# plug_in_boards.net
KiCad netlist of a schematic drawn in EAGLE
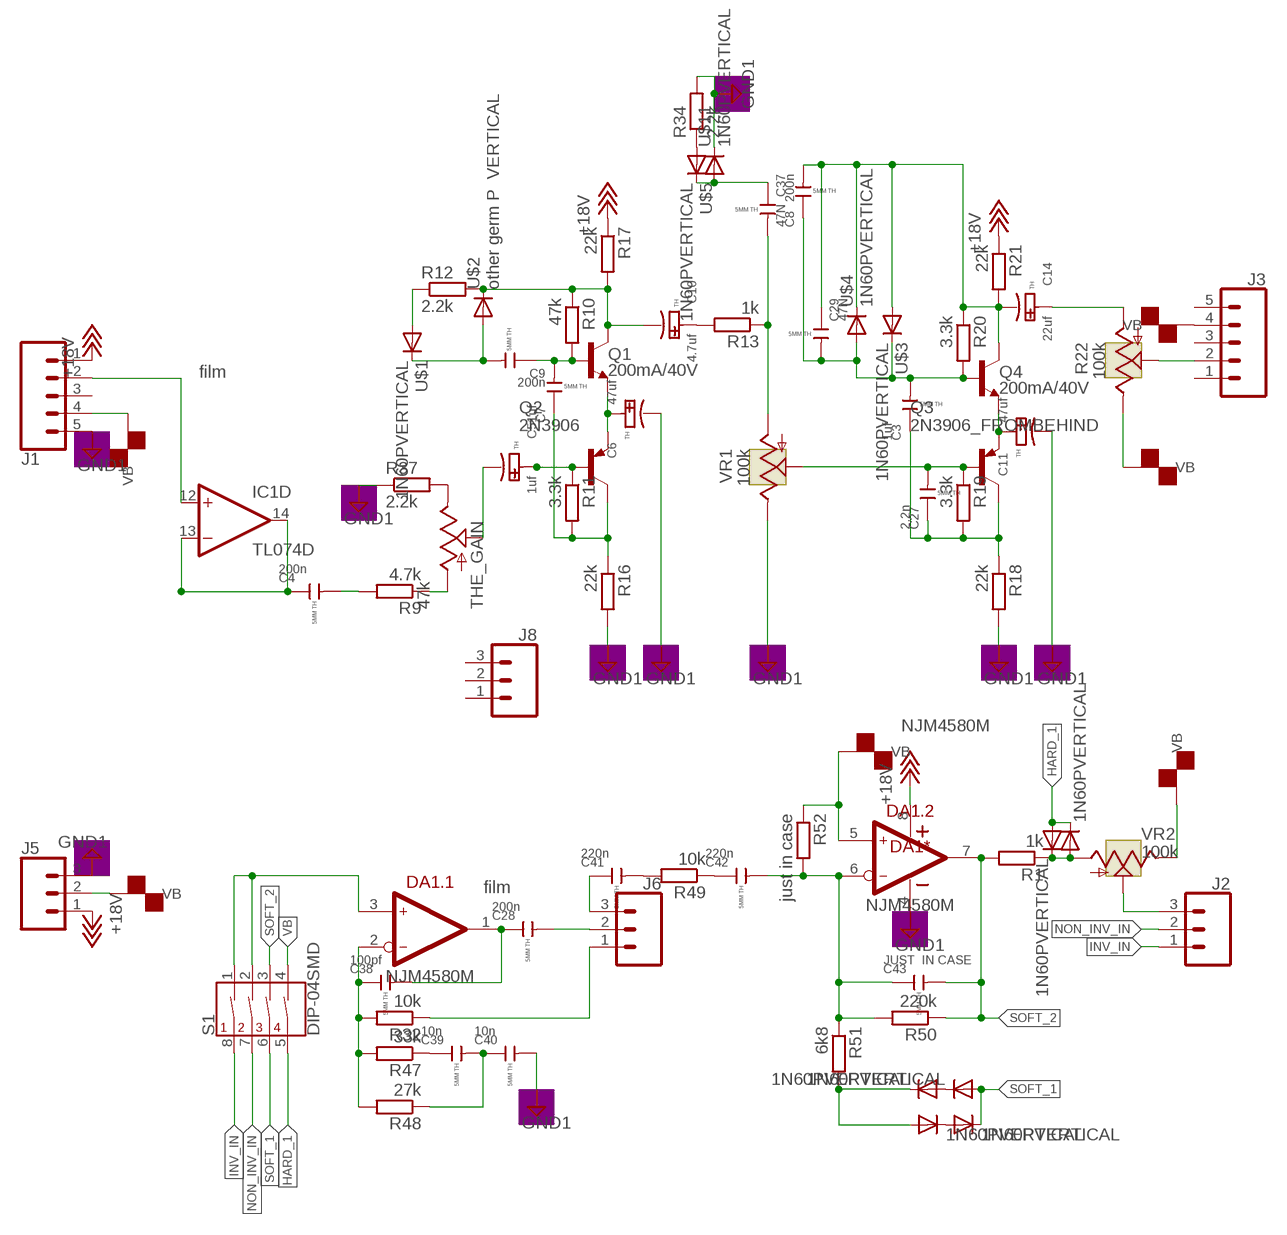
[diagram p0: schematic, sheet 1]

(export (version "E")
  (design (tool "Eeschema 10.0.6"))
  (components
    (comp (ref "C3")
      (value "1uf")
      (footprint "eagle-import:CERAMIC-5MM")
      (fields (field (name "PACKAGE") "5MM TH"))
      (libsource (lib "eagle-import") (part "THRU_HOLE_5MM_SPACING"))
    )
    (comp (ref "C4")
      (value "200n")
      (footprint "eagle-import:CERAMIC-5MM")
      (fields (field (name "PACKAGE") "5MM TH"))
      (libsource (lib "eagle-import") (part "THRU_HOLE_5MM_SPACING"))
    )
    (comp (ref "C5")
      (value "1uf")
      (footprint "eagle-import:PC-D5.3MM")
      (fields (field (name "PACKAGE") "TH"))
      (libsource (lib "eagle-import") (part "THRU-HOLE-POLARIZED"))
    )
    (comp (ref "C6")
      (value "47uf")
      (footprint "eagle-import:PC-D5.3MM")
      (fields (field (name "PACKAGE") "TH"))
      (libsource (lib "eagle-import") (part "THRU-HOLE-POLARIZED"))
    )
    (comp (ref "C7")
      (value "1uf")
      (footprint "eagle-import:CERAMIC-5MM")
      (fields (field (name "PACKAGE") "5MM TH"))
      (libsource (lib "eagle-import") (part "THRU_HOLE_5MM_SPACING"))
    )
    (comp (ref "C8")
      (value "47N")
      (footprint "eagle-import:CERAMIC-5MM")
      (fields (field (name "PACKAGE") "5MM TH"))
      (libsource (lib "eagle-import") (part "THRU_HOLE_5MM_SPACING"))
    )
    (comp (ref "C9")
      (value "200n")
      (footprint "eagle-import:CERAMIC-5MM")
      (fields (field (name "PACKAGE") "5MM TH"))
      (libsource (lib "eagle-import") (part "THRU_HOLE_5MM_SPACING"))
    )
    (comp (ref "C10")
      (value "4.7uf")
      (footprint "eagle-import:PC-D5.3MM")
      (fields (field (name "PACKAGE") "TH"))
      (libsource (lib "eagle-import") (part "THRU-HOLE-POLARIZED"))
    )
    (comp (ref "C11")
      (value "47uf")
      (footprint "eagle-import:PC-D5.3MM")
      (fields (field (name "PACKAGE") "TH"))
      (libsource (lib "eagle-import") (part "THRU-HOLE-POLARIZED"))
    )
    (comp (ref "C14")
      (value "22uf")
      (footprint "eagle-import:PC-D5.3MM")
      (fields (field (name "PACKAGE") "TH"))
      (libsource (lib "eagle-import") (part "THRU-HOLE-POLARIZED"))
    )
    (comp (ref "C27")
      (value "2.2n")
      (footprint "eagle-import:CERAMIC-5MM")
      (fields (field (name "PACKAGE") "5MM TH"))
      (libsource (lib "eagle-import") (part "THRU_HOLE_5MM_SPACING"))
    )
    (comp (ref "C28")
      (value "200n")
      (footprint "eagle-import:CERAMIC-5MM")
      (fields (field (name "PACKAGE") "5MM TH"))
      (libsource (lib "eagle-import") (part "THRU_HOLE_5MM_SPACING"))
    )
    (comp (ref "C29")
      (value "47N")
      (footprint "eagle-import:CERAMIC-5MM")
      (fields (field (name "PACKAGE") "5MM TH"))
      (libsource (lib "eagle-import") (part "THRU_HOLE_5MM_SPACING"))
    )
    (comp (ref "C37")
      (value "200n")
      (footprint "eagle-import:CERAMIC-5MM")
      (fields (field (name "PACKAGE") "5MM TH"))
      (libsource (lib "eagle-import") (part "THRU_HOLE_5MM_SPACING"))
    )
    (comp (ref "C38")
      (value "100pf")
      (footprint "eagle-import:CERAMIC-5MM")
      (fields (field (name "PACKAGE") "5MM TH"))
      (libsource (lib "eagle-import") (part "THRU_HOLE_5MM_SPACING"))
    )
    (comp (ref "C39")
      (value "10n")
      (footprint "eagle-import:CERAMIC-5MM")
      (fields (field (name "PACKAGE") "5MM TH"))
      (libsource (lib "eagle-import") (part "THRU_HOLE_5MM_SPACING"))
    )
    (comp (ref "C40")
      (value "10n")
      (footprint "eagle-import:CERAMIC-5MM")
      (fields (field (name "PACKAGE") "5MM TH"))
      (libsource (lib "eagle-import") (part "THRU_HOLE_5MM_SPACING"))
    )
    (comp (ref "C41")
      (value "220n")
      (footprint "eagle-import:CERAMIC-5MM")
      (fields (field (name "PACKAGE") "5MM TH"))
      (libsource (lib "eagle-import") (part "THRU_HOLE_5MM_SPACING"))
    )
    (comp (ref "C42")
      (value "220n")
      (footprint "eagle-import:CERAMIC-5MM")
      (fields (field (name "PACKAGE") "5MM TH"))
      (libsource (lib "eagle-import") (part "THRU_HOLE_5MM_SPACING"))
    )
    (comp (ref "C43")
      (value "JUST IN CASE")
      (footprint "eagle-import:CERAMIC-5MM")
      (fields (field (name "PACKAGE") "5MM TH"))
      (libsource (lib "eagle-import") (part "THRU_HOLE_5MM_SPACING"))
    )
    (comp (ref "DA1")
      (value "NJM4580M")
      (footprint "eagle-import:SO-8")
      (libsource (lib "eagle-import") (part "NJM4580M"))
    )
    (comp (ref "IC1")
      (value "TL074D")
      (footprint "eagle-import:SO14")
      (libsource (lib "eagle-import") (part "TL074D"))
    )
    (comp (ref "J1")
      (value "CONN_05PTH_LONGPADS")
      (footprint "eagle-import:1X05_LONGPADS")
      (libsource (lib "eagle-import") (part "CONN_05PTH_LONGPADS"))
    )
    (comp (ref "J2")
      (value "CONN_03LONGPADS")
      (footprint "eagle-import:1X03_LONGPADS")
      (libsource (lib "eagle-import") (part "CONN_03LONGPADS"))
    )
    (comp (ref "J3")
      (value "CONN_05PTH_LONGPADS")
      (footprint "eagle-import:1X05_LONGPADS")
      (libsource (lib "eagle-import") (part "CONN_05PTH_LONGPADS"))
    )
    (comp (ref "J5")
      (value "CONN_03LONGPADS")
      (footprint "eagle-import:1X03_LONGPADS")
      (libsource (lib "eagle-import") (part "CONN_03LONGPADS"))
    )
    (comp (ref "J6")
      (value "CONN_03LONGPADS")
      (footprint "eagle-import:1X03_LONGPADS")
      (libsource (lib "eagle-import") (part "CONN_03LONGPADS"))
    )
    (comp (ref "J8")
      (value "CONN_03LONGPADS")
      (footprint "eagle-import:1X03_LONGPADS")
      (libsource (lib "eagle-import") (part "CONN_03LONGPADS"))
    )
    (comp (ref "Q1")
      (value "200mA/40V")
      (footprint "eagle-import:TO-92")
      (libsource (lib "eagle-import") (part "TRANS_NPN-2N3904"))
    )
    (comp (ref "Q2")
      (value "2N3906")
      (footprint "eagle-import:TO92")
      (libsource (lib "eagle-import") (part "transistor-pnp_399_2N3906"))
    )
    (comp (ref "Q3")
      (value "2N3906_FROMBEHIND")
      (footprint "eagle-import:TO92")
      (libsource (lib "eagle-import") (part "2N3906"))
    )
    (comp (ref "Q4")
      (value "200mA/40V")
      (footprint "eagle-import:TO-92")
      (libsource (lib "eagle-import") (part "TRANS_NPN-2N3904"))
    )
    (comp (ref "R1")
      (value "1k")
      (footprint "eagle-import:R1206")
      (libsource (lib "eagle-import") (part "R-EU_R1206"))
    )
    (comp (ref "R9")
      (value "4.7k")
      (footprint "eagle-import:R1206")
      (libsource (lib "eagle-import") (part "R-EU_R1206"))
    )
    (comp (ref "R10")
      (value "47k")
      (footprint "eagle-import:R1206")
      (libsource (lib "eagle-import") (part "R-EU_R1206"))
    )
    (comp (ref "R11")
      (value "3.3k")
      (footprint "eagle-import:R1206")
      (libsource (lib "eagle-import") (part "R-EU_R1206"))
    )
    (comp (ref "R12")
      (value "2.2k")
      (footprint "eagle-import:R1206")
      (libsource (lib "eagle-import") (part "R-EU_R1206"))
    )
    (comp (ref "R13")
      (value "1k")
      (footprint "eagle-import:R1206")
      (libsource (lib "eagle-import") (part "R-EU_R1206"))
    )
    (comp (ref "R16")
      (value "22k")
      (footprint "eagle-import:R1206")
      (libsource (lib "eagle-import") (part "R-EU_R1206"))
    )
    (comp (ref "R17")
      (value "22k")
      (footprint "eagle-import:R1206")
      (libsource (lib "eagle-import") (part "R-EU_R1206"))
    )
    (comp (ref "R18")
      (value "22k")
      (footprint "eagle-import:R1206")
      (libsource (lib "eagle-import") (part "R-EU_R1206"))
    )
    (comp (ref "R19")
      (value "3.3k")
      (footprint "eagle-import:R1206")
      (libsource (lib "eagle-import") (part "R-EU_R1206"))
    )
    (comp (ref "R20")
      (value "3.3k")
      (footprint "eagle-import:R1206")
      (libsource (lib "eagle-import") (part "R-EU_R1206"))
    )
    (comp (ref "R21")
      (value "22k")
      (footprint "eagle-import:R1206")
      (libsource (lib "eagle-import") (part "R-EU_R1206"))
    )
    (comp (ref "R22")
      (value "100k")
      (footprint "eagle-import:3223G")
      (libsource (lib "eagle-import") (part "TRIM_US-3223G"))
    )
    (comp (ref "R32")
      (value "10k")
      (footprint "eagle-import:R1206")
      (libsource (lib "eagle-import") (part "R-EU_R1206"))
    )
    (comp (ref "R34")
      (value "2.2k")
      (footprint "eagle-import:R1206")
      (libsource (lib "eagle-import") (part "R-EU_R1206"))
    )
    (comp (ref "R37")
      (value "2.2k")
      (footprint "eagle-import:R1206")
      (libsource (lib "eagle-import") (part "R-EU_R1206"))
    )
    (comp (ref "R47")
      (value "33k")
      (footprint "eagle-import:R1206")
      (libsource (lib "eagle-import") (part "R-EU_R1206"))
    )
    (comp (ref "R48")
      (value "27k")
      (footprint "eagle-import:R1206")
      (libsource (lib "eagle-import") (part "R-EU_R1206"))
    )
    (comp (ref "R49")
      (value "10k")
      (footprint "eagle-import:R1206")
      (libsource (lib "eagle-import") (part "R-EU_R1206"))
    )
    (comp (ref "R50")
      (value "220k")
      (footprint "eagle-import:R1206")
      (libsource (lib "eagle-import") (part "R-EU_R1206"))
    )
    (comp (ref "R51")
      (value "6k8")
      (footprint "eagle-import:R1206")
      (libsource (lib "eagle-import") (part "R-EU_R1206"))
    )
    (comp (ref "R52")
      (value "just in case")
      (footprint "eagle-import:R1206")
      (libsource (lib "eagle-import") (part "R-EU_R1206"))
    )
    (comp (ref "S1")
      (value "DIP-04SMD")
      (footprint "eagle-import:DIPSWITCH-04-SMD")
      (libsource (lib "eagle-import") (part "DIP-04SMD"))
    )
    (comp (ref "THE_GAIN")
      (value "47k")
      (footprint "eagle-import:ALPS_POT")
      (libsource (lib "eagle-import") (part "POT"))
    )
    (comp (ref "U$1")
      (value "1N60PVERTICAL")
      (footprint "eagle-import:DO41-1")
      (libsource (lib "eagle-import") (part "1N60PVERTICAL"))
    )
    (comp (ref "U$2")
      (value "other germ P VERTICAL")
      (footprint "eagle-import:DO41-1")
      (libsource (lib "eagle-import") (part "1N60PVERTICAL"))
    )
    (comp (ref "U$3")
      (value "1N60PVERTICAL")
      (footprint "eagle-import:DO41-1")
      (libsource (lib "eagle-import") (part "1N60PVERTICAL"))
    )
    (comp (ref "U$4")
      (value "1N60PVERTICAL")
      (footprint "eagle-import:DO41-1")
      (libsource (lib "eagle-import") (part "1N60PVERTICAL"))
    )
    (comp (ref "U$5")
      (value "1N60PVERTICAL")
      (footprint "eagle-import:DO41-1")
      (libsource (lib "eagle-import") (part "1N60PVERTICAL"))
    )
    (comp (ref "U$9")
      (value "1N60PVERTICAL")
      (footprint "eagle-import:DO41-1")
      (libsource (lib "eagle-import") (part "1N60PVERTICAL"))
    )
    (comp (ref "U$11")
      (value "1N60PVERTICAL")
      (footprint "eagle-import:DO41-1")
      (libsource (lib "eagle-import") (part "1N60PVERTICAL"))
    )
    (comp (ref "U$12")
      (value "1N60PVERTICAL")
      (footprint "eagle-import:DO41-1")
      (libsource (lib "eagle-import") (part "1N60PVERTICAL"))
    )
    (comp (ref "U$26")
      (value "1N60PVERTICAL")
      (footprint "eagle-import:DO41-1")
      (libsource (lib "eagle-import") (part "1N60PVERTICAL"))
    )
    (comp (ref "U$27")
      (value "1N60PVERTICAL")
      (footprint "eagle-import:DO41-1")
      (libsource (lib "eagle-import") (part "1N60PVERTICAL"))
    )
    (comp (ref "U$28")
      (value "1N60PVERTICAL")
      (footprint "eagle-import:DO41-1")
      (libsource (lib "eagle-import") (part "1N60PVERTICAL"))
    )
    (comp (ref "U$29")
      (value "1N60PVERTICAL")
      (footprint "eagle-import:DO41-1")
      (libsource (lib "eagle-import") (part "1N60PVERTICAL"))
    )
    (comp (ref "VR1")
      (value "100k")
      (footprint "eagle-import:3223G")
      (libsource (lib "eagle-import") (part "TRIM_US-3223G"))
    )
    (comp (ref "VR2")
      (value "100k")
      (footprint "eagle-import:3223G")
      (libsource (lib "eagle-import") (part "TRIM_US-3223G"))
    )
  )
  (nets
    (net (code "1") (name "+18V") (class "Default")
      (node (ref "DA1") (pin "8") (pinfunction "V+_8") (pintype "power_in"))
      (node (ref "J1") (pin "1") (pinfunction "1_1") (pintype "passive"))
      (node (ref "J5") (pin "1") (pinfunction "1_1") (pintype "passive"))
      (node (ref "R17") (pin "1") (pinfunction "1_1") (pintype "passive"))
      (node (ref "R21") (pin "1") (pinfunction "1_1") (pintype "passive"))
    )
    (net (code "2") (name "GND1") (class "Default")
      (node (ref "C11") (pin "-") (pinfunction "-_-") (pintype "passive"))
      (node (ref "C40") (pin "2") (pinfunction "2_2") (pintype "passive"))
      (node (ref "C6") (pin "-") (pinfunction "-_-") (pintype "passive"))
      (node (ref "DA1") (pin "4") (pinfunction "V-_4") (pintype "power_in"))
      (node (ref "J1") (pin "5") (pinfunction "5_5") (pintype "passive"))
      (node (ref "J5") (pin "3") (pinfunction "3_3") (pintype "passive"))
      (node (ref "R16") (pin "2") (pinfunction "2_2") (pintype "passive"))
      (node (ref "R18") (pin "2") (pinfunction "2_2") (pintype "passive"))
      (node (ref "R34") (pin "2") (pinfunction "2_2") (pintype "passive"))
      (node (ref "R37") (pin "1") (pinfunction "1_1") (pintype "passive"))
      (node (ref "U$11") (pin "C") (pinfunction "C_C") (pintype "passive"))
      (node (ref "VR1") (pin "3") (pinfunction "E_3") (pintype "passive"))
    )
    (net (code "3") (name "HARD_1") (class "Default")
      (node (ref "S1") (pin "5") (pinfunction "4B_5") (pintype "bidirectional"))
      (node (ref "U$12") (pin "C") (pinfunction "C_C") (pintype "passive"))
      (node (ref "U$9") (pin "A") (pinfunction "A_A") (pintype "passive"))
    )
    (net (code "4") (name "INV_IN") (class "Default")
      (node (ref "J2") (pin "1") (pinfunction "1_1") (pintype "passive"))
      (node (ref "S1") (pin "8") (pinfunction "1B_8") (pintype "bidirectional"))
    )
    (net (code "5") (name "NON_INV_IN") (class "Default")
      (node (ref "J2") (pin "2") (pinfunction "2_2") (pintype "passive"))
      (node (ref "S1") (pin "7") (pinfunction "2B_7") (pintype "bidirectional"))
    )
    (net (code "6") (name "Net-(C4-Pad2)") (class "Default")
      (node (ref "C4") (pin "2") (pinfunction "2_2") (pintype "passive"))
      (node (ref "R9") (pin "2") (pinfunction "2_2") (pintype "passive"))
    )
    (net (code "7") (name "Net-(C9-Pad2)") (class "Default")
      (node (ref "C9") (pin "2") (pinfunction "2_2") (pintype "passive"))
      (node (ref "U$1") (pin "C") (pinfunction "C_C") (pintype "passive"))
      (node (ref "U$2") (pin "A") (pinfunction "A_A") (pintype "passive"))
    )
    (net (code "8") (name "Net-(C10-Pad+)") (class "Default")
      (node (ref "C10") (pin "+") (pinfunction "+_+") (pintype "passive"))
      (node (ref "R13") (pin "2") (pinfunction "2_2") (pintype "passive"))
    )
    (net (code "9") (name "Net-(C28-Pad2)") (class "Default")
      (node (ref "C28") (pin "2") (pinfunction "2_2") (pintype "passive"))
      (node (ref "J6") (pin "2") (pinfunction "2_2") (pintype "passive"))
    )
    (net (code "10") (name "Net-(C37-Pad1)") (class "Default")
      (node (ref "C37") (pin "1") (pinfunction "1_1") (pintype "passive"))
      (node (ref "U$11") (pin "A") (pinfunction "A_A") (pintype "passive"))
      (node (ref "U$5") (pin "C") (pinfunction "C_C") (pintype "passive"))
    )
    (net (code "11") (name "Net-(C39-Pad1)") (class "Default")
      (node (ref "C39") (pin "1") (pinfunction "1_1") (pintype "passive"))
      (node (ref "R47") (pin "1") (pinfunction "1_1") (pintype "passive"))
    )
    (net (code "12") (name "Net-(C39-Pad2)") (class "Default")
      (node (ref "C39") (pin "2") (pinfunction "2_2") (pintype "passive"))
      (node (ref "C40") (pin "1") (pinfunction "1_1") (pintype "passive"))
      (node (ref "R48") (pin "1") (pinfunction "1_1") (pintype "passive"))
    )
    (net (code "13") (name "Net-(C41-Pad1)") (class "Default")
      (node (ref "C41") (pin "1") (pinfunction "1_1") (pintype "passive"))
      (node (ref "J6") (pin "3") (pinfunction "3_3") (pintype "passive"))
    )
    (net (code "14") (name "Net-(C41-Pad2)") (class "Default")
      (node (ref "C41") (pin "2") (pinfunction "2_2") (pintype "passive"))
      (node (ref "R49") (pin "2") (pinfunction "2_2") (pintype "passive"))
    )
    (net (code "15") (name "Net-(C42-Pad1)") (class "Default")
      (node (ref "C42") (pin "1") (pinfunction "1_1") (pintype "passive"))
      (node (ref "R49") (pin "1") (pinfunction "1_1") (pintype "passive"))
    )
    (net (code "16") (name "Net-(DA1B-IN+)") (class "Default")
      (node (ref "DA1") (pin "3") (pinfunction "IN+_3") (pintype "input"))
      (node (ref "S1") (pin "1") (pinfunction "1A_1") (pintype "bidirectional"))
      (node (ref "S1") (pin "2") (pinfunction "2A_2") (pintype "bidirectional"))
    )
    (net (code "17") (name "Net-(DA1B-IN-)") (class "Default")
      (node (ref "C38") (pin "1") (pinfunction "1_1") (pintype "passive"))
      (node (ref "DA1") (pin "2") (pinfunction "IN-_2") (pintype "input"))
      (node (ref "R32") (pin "2") (pinfunction "2_2") (pintype "passive"))
      (node (ref "R47") (pin "2") (pinfunction "2_2") (pintype "passive"))
      (node (ref "R48") (pin "2") (pinfunction "2_2") (pintype "passive"))
    )
    (net (code "18") (name "Net-(DA1B-OUT)") (class "Default")
      (node (ref "C28") (pin "1") (pinfunction "1_1") (pintype "passive"))
      (node (ref "C38") (pin "2") (pinfunction "2_2") (pintype "passive"))
      (node (ref "DA1") (pin "1") (pinfunction "OUT_1") (pintype "output"))
    )
    (net (code "19") (name "Net-(DA1C-IN-)") (class "Default")
      (node (ref "C42") (pin "2") (pinfunction "2_2") (pintype "passive"))
      (node (ref "C43") (pin "1") (pinfunction "1_1") (pintype "passive"))
      (node (ref "DA1") (pin "6") (pinfunction "IN-_6") (pintype "input"))
      (node (ref "R50") (pin "2") (pinfunction "2_2") (pintype "passive"))
      (node (ref "R51") (pin "1") (pinfunction "1_1") (pintype "passive"))
      (node (ref "R52") (pin "2") (pinfunction "2_2") (pintype "passive"))
    )
    (net (code "20") (name "Net-(IC1D-+IN)") (class "Default")
      (node (ref "IC1") (pin "12") (pinfunction "+IN_12") (pintype "input"))
      (node (ref "J1") (pin "2") (pinfunction "2_2") (pintype "passive"))
    )
    (net (code "21") (name "Net-(IC1D--IN)") (class "Default")
      (node (ref "C4") (pin "1") (pinfunction "1_1") (pintype "passive"))
      (node (ref "IC1") (pin "13") (pinfunction "-IN_13") (pintype "input"))
      (node (ref "IC1") (pin "14") (pinfunction "OUT_14") (pintype "output"))
    )
    (net (code "22") (name "Net-(J6-Pad1)") (class "Default")
      (node (ref "J6") (pin "1") (pinfunction "1_1") (pintype "passive"))
      (node (ref "R32") (pin "1") (pinfunction "1_1") (pintype "passive"))
    )
    (net (code "23") (name "Net-(Q1-B)") (class "Default")
      (node (ref "C7") (pin "2") (pinfunction "2_2") (pintype "passive"))
      (node (ref "C9") (pin "1") (pinfunction "1_1") (pintype "passive"))
      (node (ref "Q1") (pin "2") (pinfunction "B_2") (pintype "passive"))
      (node (ref "R10") (pin "2") (pinfunction "2_2") (pintype "passive"))
    )
    (net (code "24") (name "Net-(Q1-C)") (class "Default")
      (node (ref "C10") (pin "-") (pinfunction "-_-") (pintype "passive"))
      (node (ref "Q1") (pin "3") (pinfunction "C_3") (pintype "passive"))
      (node (ref "R10") (pin "1") (pinfunction "1_1") (pintype "passive"))
      (node (ref "R12") (pin "2") (pinfunction "2_2") (pintype "passive"))
      (node (ref "R17") (pin "2") (pinfunction "2_2") (pintype "passive"))
      (node (ref "U$2") (pin "C") (pinfunction "C_C") (pintype "passive"))
    )
    (net (code "25") (name "Net-(Q1-E)") (class "Default")
      (node (ref "C6") (pin "+") (pinfunction "+_+") (pintype "passive"))
      (node (ref "Q1") (pin "1") (pinfunction "E_1") (pintype "passive"))
      (node (ref "Q2") (pin "3") (pinfunction "E_3") (pintype "passive"))
    )
    (net (code "26") (name "Net-(Q2-B)") (class "Default")
      (node (ref "C5") (pin "+") (pinfunction "+_+") (pintype "passive"))
      (node (ref "Q2") (pin "2") (pinfunction "B_2") (pintype "passive"))
      (node (ref "R11") (pin "1") (pinfunction "1_1") (pintype "passive"))
    )
    (net (code "27") (name "Net-(Q2-C)") (class "Default")
      (node (ref "C7") (pin "1") (pinfunction "1_1") (pintype "passive"))
      (node (ref "Q2") (pin "1") (pinfunction "C_1") (pintype "passive"))
      (node (ref "R11") (pin "2") (pinfunction "2_2") (pintype "passive"))
      (node (ref "R16") (pin "1") (pinfunction "1_1") (pintype "passive"))
    )
    (net (code "28") (name "Net-(Q3-B)") (class "Default")
      (node (ref "C27") (pin "2") (pinfunction "2_2") (pintype "passive"))
      (node (ref "Q3") (pin "2") (pinfunction "B_2") (pintype "passive"))
      (node (ref "R19") (pin "1") (pinfunction "1_1") (pintype "passive"))
      (node (ref "VR1") (pin "2") (pinfunction "S_2") (pintype "passive"))
    )
    (net (code "29") (name "Net-(Q3-C)") (class "Default")
      (node (ref "C27") (pin "1") (pinfunction "1_1") (pintype "passive"))
      (node (ref "C3") (pin "1") (pinfunction "1_1") (pintype "passive"))
      (node (ref "Q3") (pin "1") (pinfunction "C_1") (pintype "passive"))
      (node (ref "R18") (pin "1") (pinfunction "1_1") (pintype "passive"))
      (node (ref "R19") (pin "2") (pinfunction "2_2") (pintype "passive"))
    )
    (net (code "30") (name "Net-(Q3-E)") (class "Default")
      (node (ref "C11") (pin "+") (pinfunction "+_+") (pintype "passive"))
      (node (ref "Q3") (pin "3") (pinfunction "E_3") (pintype "passive"))
      (node (ref "Q4") (pin "1") (pinfunction "E_1") (pintype "passive"))
    )
    (net (code "31") (name "Net-(Q4-B)") (class "Default")
      (node (ref "C29") (pin "2") (pinfunction "2_2") (pintype "passive"))
      (node (ref "C3") (pin "2") (pinfunction "2_2") (pintype "passive"))
      (node (ref "C8") (pin "1") (pinfunction "1_1") (pintype "passive"))
      (node (ref "Q4") (pin "2") (pinfunction "B_2") (pintype "passive"))
      (node (ref "R20") (pin "2") (pinfunction "2_2") (pintype "passive"))
      (node (ref "U$3") (pin "C") (pinfunction "C_C") (pintype "passive"))
      (node (ref "U$4") (pin "A") (pinfunction "A_A") (pintype "passive"))
    )
    (net (code "32") (name "Net-(Q4-C)") (class "Default")
      (node (ref "C14") (pin "-") (pinfunction "-_-") (pintype "passive"))
      (node (ref "C29") (pin "1") (pinfunction "1_1") (pintype "passive"))
      (node (ref "C8") (pin "2") (pinfunction "2_2") (pintype "passive"))
      (node (ref "Q4") (pin "3") (pinfunction "C_3") (pintype "passive"))
      (node (ref "R20") (pin "1") (pinfunction "1_1") (pintype "passive"))
      (node (ref "R21") (pin "2") (pinfunction "2_2") (pintype "passive"))
      (node (ref "U$3") (pin "A") (pinfunction "A_A") (pintype "passive"))
      (node (ref "U$4") (pin "C") (pinfunction "C_C") (pintype "passive"))
    )
    (net (code "33") (name "Net-(R12-Pad1)") (class "Default")
      (node (ref "R12") (pin "1") (pinfunction "1_1") (pintype "passive"))
      (node (ref "U$1") (pin "A") (pinfunction "A_A") (pintype "passive"))
    )
    (net (code "34") (name "Net-(R22-A)") (class "Default")
      (node (ref "C14") (pin "+") (pinfunction "+_+") (pintype "passive"))
      (node (ref "R22") (pin "1") (pinfunction "A_1") (pintype "passive"))
    )
    (net (code "35") (name "Net-(R22-S)") (class "Default")
      (node (ref "J3") (pin "2") (pinfunction "2_2") (pintype "passive"))
      (node (ref "R22") (pin "2") (pinfunction "S_2") (pintype "passive"))
    )
    (net (code "36") (name "Net-(R34-Pad1)") (class "Default")
      (node (ref "R34") (pin "1") (pinfunction "1_1") (pintype "passive"))
      (node (ref "U$5") (pin "A") (pinfunction "A_A") (pintype "passive"))
    )
    (net (code "37") (name "Net-(R51-Pad2)") (class "Default")
      (node (ref "R51") (pin "2") (pinfunction "2_2") (pintype "passive"))
      (node (ref "U$27") (pin "C") (pinfunction "C_C") (pintype "passive"))
      (node (ref "U$28") (pin "A") (pinfunction "A_A") (pintype "passive"))
    )
    (net (code "38") (name "Net-(THE_GAIN-A)") (class "Default")
      (node (ref "R9") (pin "1") (pinfunction "1_1") (pintype "passive"))
      (node (ref "THE_GAIN") (pin "P$3") (pinfunction "A_P$3") (pintype "passive"))
    )
    (net (code "39") (name "Net-(THE_GAIN-E)") (class "Default")
      (node (ref "R37") (pin "2") (pinfunction "2_2") (pintype "passive"))
      (node (ref "THE_GAIN") (pin "P$1") (pinfunction "E_P$1") (pintype "passive"))
    )
    (net (code "40") (name "Net-(THE_GAIN-S)") (class "Default")
      (node (ref "C5") (pin "-") (pinfunction "-_-") (pintype "passive"))
      (node (ref "THE_GAIN") (pin "P$2") (pinfunction "S_P$2") (pintype "passive"))
    )
    (net (code "41") (name "Net-(U$26-PadC)") (class "Default")
      (node (ref "U$26") (pin "C") (pinfunction "C_C") (pintype "passive"))
      (node (ref "U$27") (pin "A") (pinfunction "A_A") (pintype "passive"))
    )
    (net (code "42") (name "Net-(U$28-PadC)") (class "Default")
      (node (ref "U$28") (pin "C") (pinfunction "C_C") (pintype "passive"))
      (node (ref "U$29") (pin "A") (pinfunction "A_A") (pintype "passive"))
    )
    (net (code "43") (name "Net-(VR1-A)") (class "Default")
      (node (ref "C37") (pin "2") (pinfunction "2_2") (pintype "passive"))
      (node (ref "R13") (pin "1") (pinfunction "1_1") (pintype "passive"))
      (node (ref "VR1") (pin "1") (pinfunction "A_1") (pintype "passive"))
    )
    (net (code "44") (name "Net-(VR2-A)") (class "Default")
      (node (ref "R1") (pin "1") (pinfunction "1_1") (pintype "passive"))
      (node (ref "U$12") (pin "A") (pinfunction "A_A") (pintype "passive"))
      (node (ref "U$9") (pin "C") (pinfunction "C_C") (pintype "passive"))
      (node (ref "VR2") (pin "1") (pinfunction "A_1") (pintype "passive"))
    )
    (net (code "45") (name "Net-(VR2-S)") (class "Default")
      (node (ref "J2") (pin "3") (pinfunction "3_3") (pintype "passive"))
      (node (ref "VR2") (pin "2") (pinfunction "S_2") (pintype "passive"))
    )
    (net (code "46") (name "SOFT_1") (class "Default")
      (node (ref "S1") (pin "6") (pinfunction "3B_6") (pintype "bidirectional"))
      (node (ref "U$26") (pin "A") (pinfunction "A_A") (pintype "passive"))
      (node (ref "U$29") (pin "C") (pinfunction "C_C") (pintype "passive"))
    )
    (net (code "47") (name "SOFT_2") (class "Default")
      (node (ref "C43") (pin "2") (pinfunction "2_2") (pintype "passive"))
      (node (ref "DA1") (pin "7") (pinfunction "OUT_7") (pintype "output"))
      (node (ref "R1") (pin "2") (pinfunction "2_2") (pintype "passive"))
      (node (ref "R50") (pin "1") (pinfunction "1_1") (pintype "passive"))
      (node (ref "S1") (pin "3") (pinfunction "3A_3") (pintype "bidirectional"))
    )
    (net (code "48") (name "VB") (class "Default")
      (node (ref "DA1") (pin "5") (pinfunction "IN+_5") (pintype "input"))
      (node (ref "J1") (pin "4") (pinfunction "4_4") (pintype "passive"))
      (node (ref "J3") (pin "4") (pinfunction "4_4") (pintype "passive"))
      (node (ref "J5") (pin "2") (pinfunction "2_2") (pintype "passive"))
      (node (ref "R22") (pin "3") (pinfunction "E_3") (pintype "passive"))
      (node (ref "R52") (pin "1") (pinfunction "1_1") (pintype "passive"))
      (node (ref "S1") (pin "4") (pinfunction "4A_4") (pintype "bidirectional"))
      (node (ref "VR2") (pin "3") (pinfunction "E_3") (pintype "passive"))
    )
    (net (code "49") (name "unconnected-(J1-Pad3)") (class "Default")
      (node (ref "J1") (pin "3") (pinfunction "3_3") (pintype "passive"))
    )
    (net (code "50") (name "unconnected-(J3-Pad1)") (class "Default")
      (node (ref "J3") (pin "1") (pinfunction "1_1") (pintype "passive"))
    )
    (net (code "51") (name "unconnected-(J3-Pad3)") (class "Default")
      (node (ref "J3") (pin "3") (pinfunction "3_3") (pintype "passive"))
    )
    (net (code "52") (name "unconnected-(J3-Pad5)") (class "Default")
      (node (ref "J3") (pin "5") (pinfunction "5_5") (pintype "passive"))
    )
    (net (code "53") (name "unconnected-(J8-Pad1)") (class "Default")
      (node (ref "J8") (pin "1") (pinfunction "1_1") (pintype "passive"))
    )
    (net (code "54") (name "unconnected-(J8-Pad2)") (class "Default")
      (node (ref "J8") (pin "2") (pinfunction "2_2") (pintype "passive"))
    )
    (net (code "55") (name "unconnected-(J8-Pad3)") (class "Default")
      (node (ref "J8") (pin "3") (pinfunction "3_3") (pintype "passive"))
    )
  )
)
